# BlueFlower_POT.net
KiCad netlist of a schematic drawn in Altium Designer
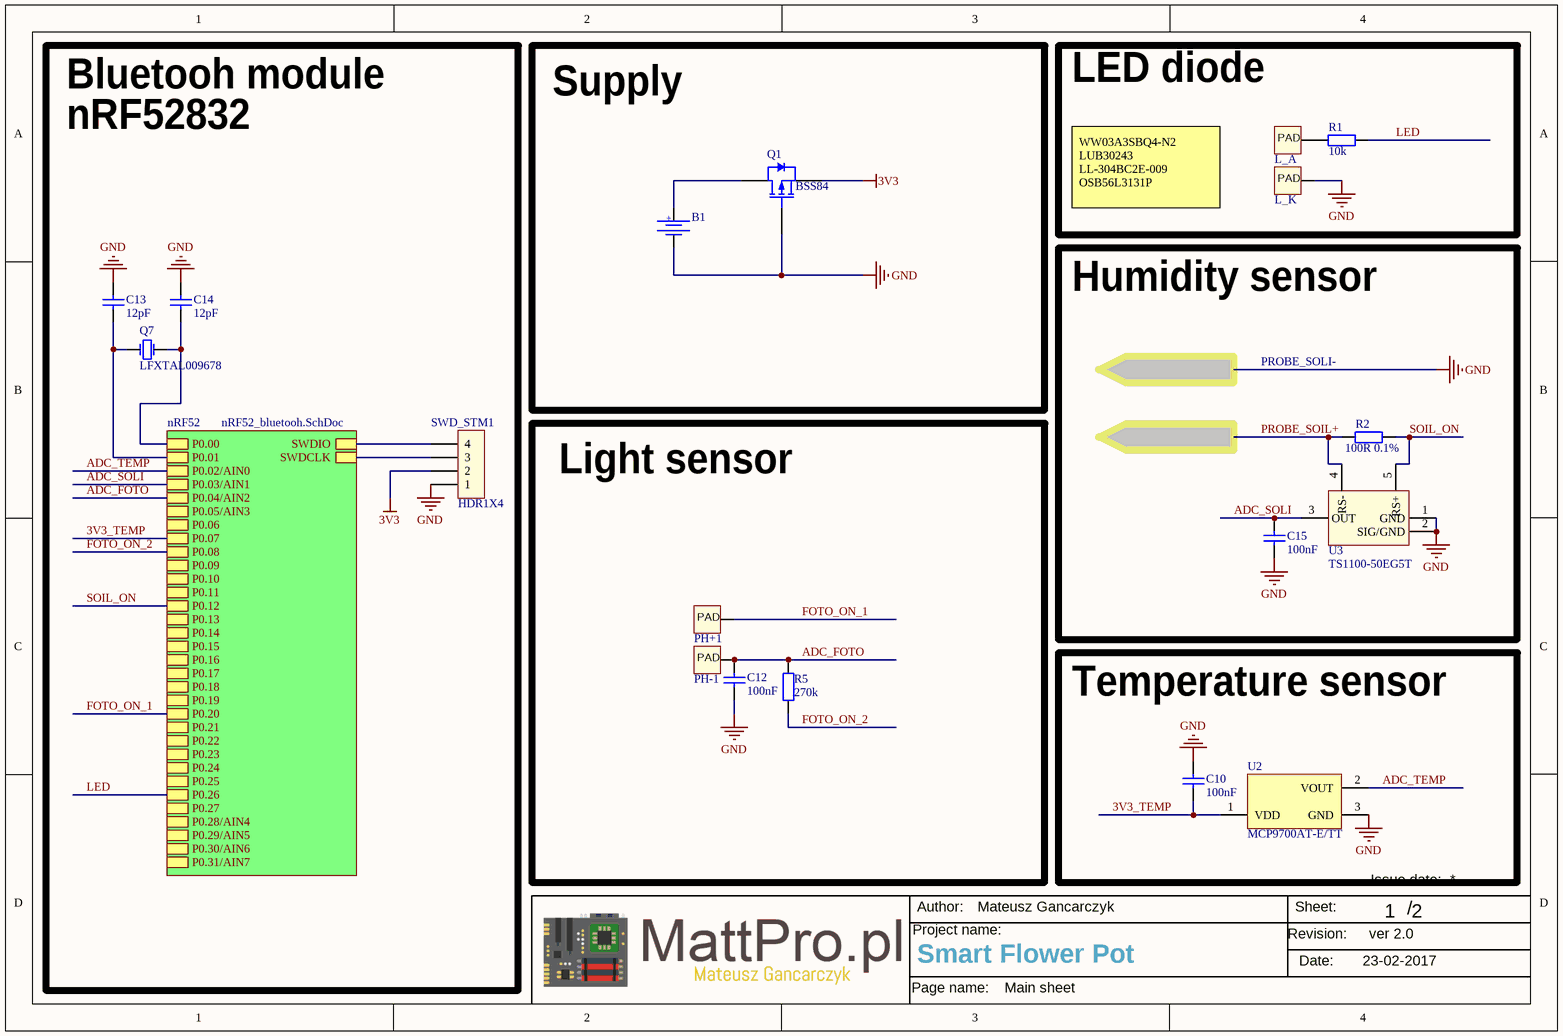
[diagram p0: BlueFlower POT.SchDoc]

(export (version "E")
  (design (tool "Eeschema 10.0.6"))
  (components
    (comp (ref "B1")
      (value "BC-2001")
      (footprint "CR2032_HOLDER_SMD")
      (description "Bat Holder CR2032 SMD")
      (fields
        (field (name "MANUFACTURER") "Comfortable")
        (field (name "2ND SOURCE PART NUMBER") "165-0693")
        (field (name "PUBLISHER") "Nordic Semiconductor")
      )
      (libsource (lib "pca10040") (part "Battery"))
    )
    (comp (ref "C10")
      (value "0603 100nF 20V")
      (footprint "SMD 0603S - CAPACITOR")
      (description "Kondensator")
      (fields (field (name "WARTOŚĆ") "100nF"))
      (libsource (lib "MY_LIB") (part "Kondensator SMD"))
    )
    (comp (ref "C12")
      (value "0603 100nF 20V")
      (footprint "SMD 0603S - CAPACITOR")
      (description "Kondensator")
      (fields (field (name "WARTOŚĆ") "100nF"))
      (libsource (lib "MY_LIB") (part "Kondensator SMD"))
    )
    (comp (ref "C13")
      (value "0603 12pF 20V")
      (footprint "SMD 0603S - CAPACITOR")
      (description "Kondensator")
      (fields (field (name "WARTOŚĆ") "12pF"))
      (libsource (lib "MY_LIB") (part "Kondensator SMD"))
    )
    (comp (ref "C14")
      (value "0603 12pF 20V")
      (footprint "SMD 0603S - CAPACITOR")
      (description "Kondensator")
      (fields (field (name "WARTOŚĆ") "12pF"))
      (libsource (lib "MY_LIB") (part "Kondensator SMD"))
    )
    (comp (ref "C15")
      (value "0603 100nF 20V")
      (footprint "SMD 0603S - CAPACITOR")
      (description "Kondensator")
      (fields (field (name "WARTOŚĆ") "100nF"))
      (libsource (lib "MY_LIB") (part "Kondensator SMD"))
    )
    (comp (ref "L_A")
      (value "Pad lutowniczy")
      (footprint "PAD_3x0.8mm")
      (libsource (lib "MY_LIB") (part "Pad"))
    )
    (comp (ref "L_K")
      (value "Pad lutowniczy")
      (footprint "PAD_3x0.8mm")
      (libsource (lib "MY_LIB") (part "Pad"))
    )
    (comp (ref "PH+1")
      (value "Pad lutowniczy")
      (footprint "PAD_3x0.8mm")
      (libsource (lib "MY_LIB") (part "Pad"))
    )
    (comp (ref "PH-1")
      (value "Pad lutowniczy")
      (footprint "PAD_3x0.8mm")
      (libsource (lib "MY_LIB") (part "Pad"))
    )
    (comp (ref "Q1")
      (value "BSS84")
      (footprint "SOT-23A")
      (description "Tranzystor MOSFET kanał P")
      (fields (field (name "WARTOŚĆ") "BSS84") (field (name "PUBLISHER") "Altium Limited"))
      (libsource (lib "MY_LIB") (part "BSS84"))
    )
    (comp (ref "Q7")
      (value "LFXTAL009678")
      (footprint "Kwarc SMD 3.2 na 1.5mm")
      (description "Kwarc 32kHz SMD")
      (libsource (lib "MY_LIB") (part "LFXTAL009678"))
    )
    (comp (ref "R1")
      (value "0603 10k 1% 0.25W")
      (footprint "SMD 0603")
      (description "Rezystor")
      (fields (field (name "WARTOSC") "10k"))
      (libsource (lib "") (part "Rezystor SMD_1"))
    )
    (comp (ref "R2")
      (value "0805 100R 0.1% 0.25W")
      (footprint "SMD 0805")
      (description "Rezystor")
      (fields (field (name "WARTOSC") "100R 0.1%"))
      (libsource (lib "") (part "Rezystor SMD_1"))
    )
    (comp (ref "R5")
      (value "0603 270k 1% 0.25W")
      (footprint "SMD 0603")
      (description "Rezystor")
      (fields (field (name "WARTOSC") "270k"))
      (libsource (lib "MY_LIB") (part "Rezystor SMD"))
    )
    (comp (ref "SWD_STM1")
      (value "HDR1X4")
      (footprint "HDR1x4_1.27mm")
      (description "Pin header 1x4")
      (libsource (lib "Main") (part "HDR1X4"))
    )
    (comp (ref "U2")
      (value "MCP9700AT-E/TT")
      (footprint "SOT-23-TT3_N")
      (description "Czujnik Temperatury")
      (fields (field (name "MANUFACTURER") "Microchip"))
      (libsource (lib "Microchip Thermal Management") (part "MCP9700AT-E/TT"))
    )
    (comp (ref "U3")
      (value "TS1100-50EG5T")
      (footprint "SOT-23")
      (description "Low-power current sense")
      (fields (field (name "WARTOŚĆ") "TS1100-50EG5T"))
      (libsource (lib "MY_LIB") (part "TS1100"))
    )
  )
  (nets
    (net (code "1") (name "/3V3_TEMP") (class "Default")
      (node (ref "C10") (pin "1") (pinfunction "1_1") (pintype "passive"))
      (node (ref "U2") (pin "1") (pinfunction "VDD_1") (pintype "power_in"))
    )
    (net (code "2") (name "/ADC_FOTO") (class "Default")
      (node (ref "C12") (pin "2") (pinfunction "2_2") (pintype "passive"))
      (node (ref "PH-1") (pin "1") (pinfunction "1_1") (pintype "passive"))
      (node (ref "R5") (pin "1") (pinfunction "1_1") (pintype "passive"))
    )
    (net (code "3") (name "/ADC_SOLI") (class "Default")
      (node (ref "C15") (pin "2") (pinfunction "2_2") (pintype "passive"))
      (node (ref "U3") (pin "3") (pinfunction "OUT_3") (pintype "passive"))
    )
    (net (code "4") (name "/ADC_TEMP") (class "Default")
      (node (ref "U2") (pin "2") (pinfunction "VOUT_2") (pintype "power_in"))
    )
    (net (code "5") (name "/FOTO_ON_1") (class "Default")
      (node (ref "PH+1") (pin "1") (pinfunction "1_1") (pintype "passive"))
    )
    (net (code "6") (name "/FOTO_ON_2") (class "Default")
      (node (ref "R5") (pin "2") (pinfunction "2_2") (pintype "passive"))
    )
    (net (code "7") (name "/LED") (class "Default")
      (node (ref "R1") (pin "2") (pinfunction "2_2") (pintype "passive"))
    )
    (net (code "8") (name "/P0.00") (class "Default")
      (node (ref "C14") (pin "1") (pinfunction "1_1") (pintype "passive"))
      (node (ref "Q7") (pin "2") (pinfunction "2_2") (pintype "passive"))
    )
    (net (code "9") (name "/P0.01") (class "Default")
      (node (ref "C13") (pin "1") (pinfunction "1_1") (pintype "passive"))
      (node (ref "Q7") (pin "1") (pinfunction "1_1") (pintype "passive"))
    )
    (net (code "32") (name "/PROBE_SOIL+") (class "Default")
      (node (ref "R2") (pin "1") (pinfunction "1_1") (pintype "passive"))
      (node (ref "U3") (pin "4") (pinfunction "RS-_4") (pintype "passive"))
    )
    (net (code "33") (name "/SOIL_ON") (class "Default")
      (node (ref "R2") (pin "2") (pinfunction "2_2") (pintype "passive"))
      (node (ref "U3") (pin "5") (pinfunction "RS+_5") (pintype "passive"))
    )
    (net (code "34") (name "/SWDCLK") (class "Default")
      (node (ref "SWD_STM1") (pin "3") (pinfunction "3_3") (pintype "passive"))
    )
    (net (code "35") (name "/SWDIO") (class "Default")
      (node (ref "SWD_STM1") (pin "4") (pinfunction "4_4") (pintype "passive"))
    )
    (net (code "36") (name "3V3") (class "Default")
      (node (ref "Q1") (pin "2") (pinfunction "S_2") (pintype "passive"))
      (node (ref "SWD_STM1") (pin "2") (pinfunction "2_2") (pintype "passive"))
    )
    (net (code "37") (name "GND") (class "Default")
      (node (ref "B1") (pin "2") (pintype "passive"))
      (node (ref "C10") (pin "2") (pinfunction "2_2") (pintype "passive"))
      (node (ref "C12") (pin "1") (pinfunction "1_1") (pintype "passive"))
      (node (ref "C13") (pin "2") (pinfunction "2_2") (pintype "passive"))
      (node (ref "C14") (pin "2") (pinfunction "2_2") (pintype "passive"))
      (node (ref "C15") (pin "1") (pinfunction "1_1") (pintype "passive"))
      (node (ref "L_K") (pin "1") (pinfunction "1_1") (pintype "passive"))
      (node (ref "Q1") (pin "1") (pinfunction "G_1") (pintype "passive"))
      (node (ref "SWD_STM1") (pin "1") (pinfunction "1_1") (pintype "passive"))
      (node (ref "U2") (pin "3") (pinfunction "GND_3") (pintype "power_in"))
      (node (ref "U3") (pin "1") (pinfunction "GND_1") (pintype "passive"))
      (node (ref "U3") (pin "2") (pinfunction "SIG/GND_2") (pintype "passive"))
    )
    (net (code "38") (name "Net-(L_A-Pad1)") (class "Default")
      (node (ref "L_A") (pin "1") (pinfunction "1_1") (pintype "passive"))
      (node (ref "R1") (pin "1") (pinfunction "1_1") (pintype "passive"))
    )
    (net (code "39") (name "Net-(Q1-D)") (class "Default")
      (node (ref "B1") (pin "1") (pintype "passive"))
      (node (ref "Q1") (pin "3") (pinfunction "D_3") (pintype "passive"))
    )
  )
)
